# SCH_LM2596_2023-11-16.net
KiCad netlist of a schematic drawn in EasyEDA
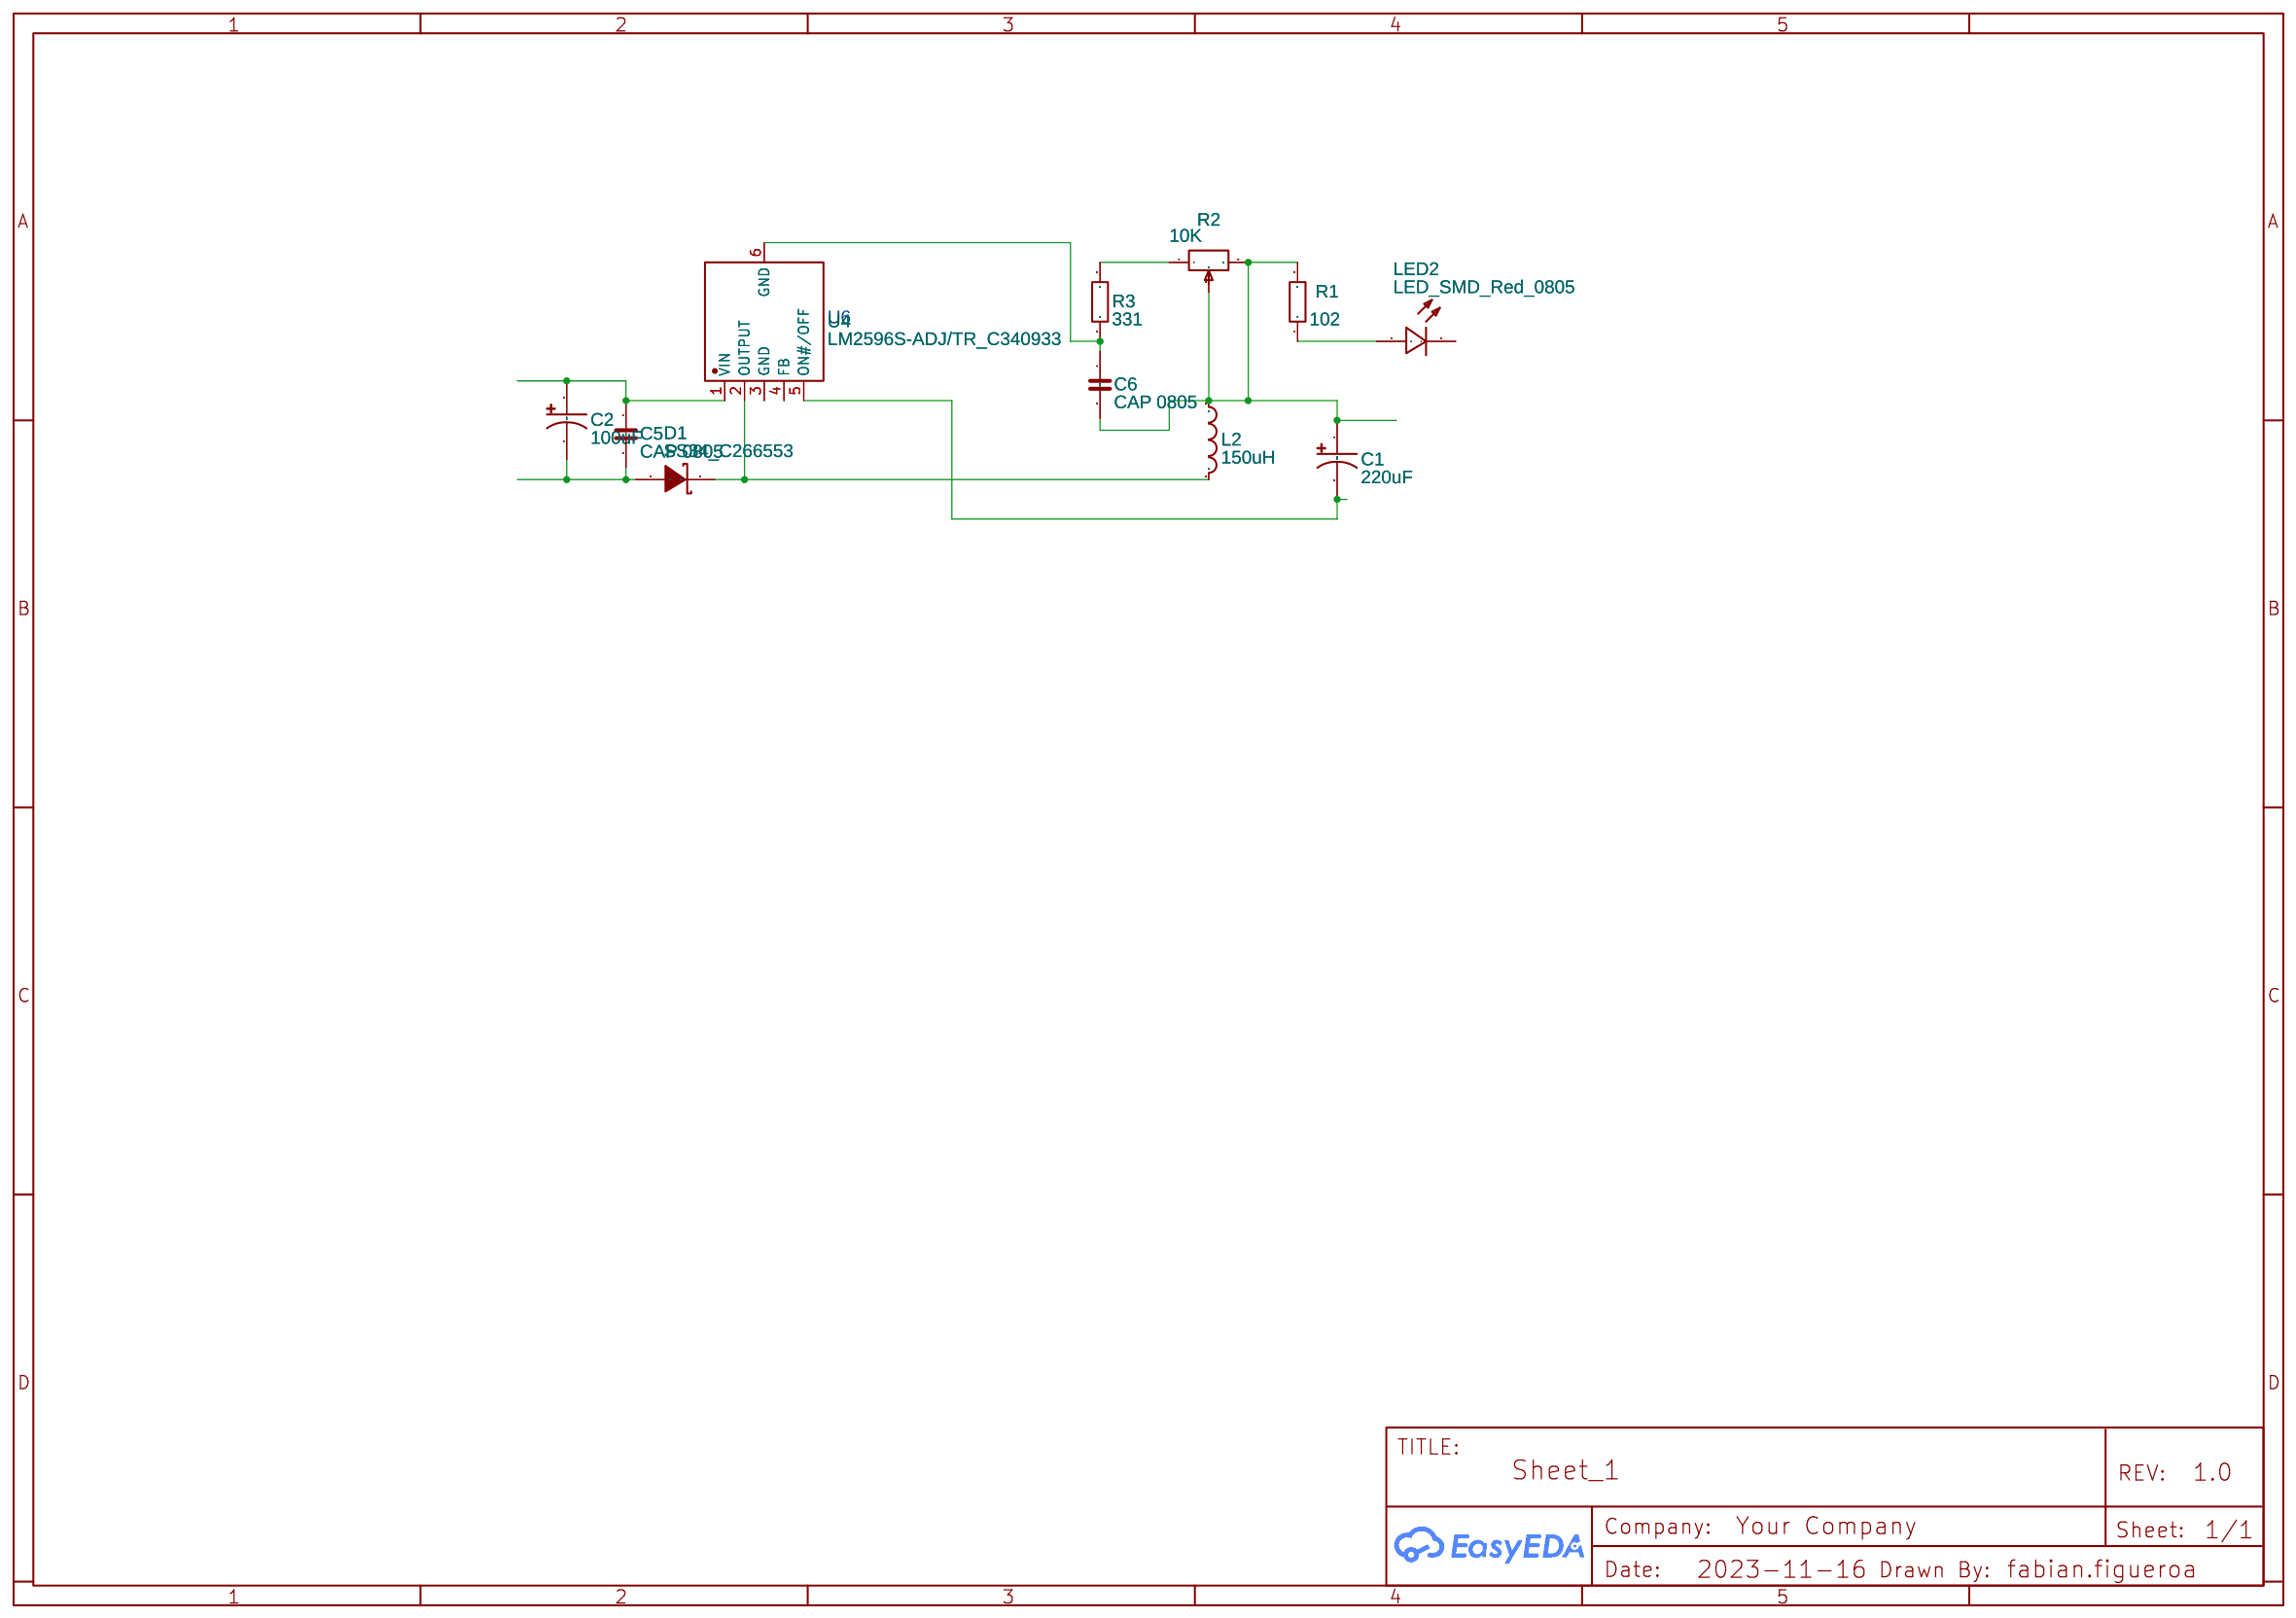
[diagram p0: schematic sheet]

(export (version "E")
  (design (tool "Eeschema 10.0.6"))
  (components
    (comp (ref "C1")
      (value "220uF")
      (fields
        (field (name "Manufacturer Part") "MVK35VC220M8*10_8.0TP")
        (field (name "Manufacturer") "SamYoung Electronics")
      )
      (libsource (lib "") (part "MVK35VC220M8*10_8.0TP"))
    )
    (comp (ref "C2")
      (value "100uF")
      (fields
        (field (name "Manufacturer Part") "BXJ-35V100-8*10")
        (field (name "Manufacturer") "SamYoung Electronics")
      )
      (libsource (lib "") (part "BXJ-35V100-8*10"))
    )
    (comp (ref "C5") (value "CAP 0805") (libsource (lib "") (part "CAP 0805")))
    (comp (ref "C6") (value "CAP 0805") (libsource (lib "") (part "CAP 0805")))
    (comp (ref "D1")
      (value "SS34_C266553")
      (fields
        (field (name "Manufacturer Part") "SS34")
        (field (name "Manufacturer") "Bourne Semicon (Shenzhen)")
      )
      (libsource (lib "") (part "SS34_C266553"))
    )
    (comp (ref "L2")
      (value "150uH")
      (fields (field (name "Manufacturer Part") "CDRH127/LDNP-151MC") (field (name "Manufacturer") "Sumida"))
      (libsource (lib "") (part "CDRH127/LDNP-151MC"))
    )
    (comp (ref "LED2")
      (value "LED_SMD_Red_0805")
      (fields
        (field (name "Manufacturer Part") "17-21SURC/S530-A2/TR8")
        (field (name "Manufacturer") "Everlight Elec")
      )
      (libsource (lib "") (part "LED_SMD_Red_0805"))
    )
    (comp (ref "R1") (value "102") (libsource (lib "") (part "RES 0805")))
    (comp (ref "R2")
      (value "10K")
      (fields (field (name "Manufacturer Part") "3296W-1-103LF") (field (name "Manufacturer") "BOURNS"))
      (libsource (lib "") (part "3296W-1-103LF"))
    )
    (comp (ref "R3") (value "331") (libsource (lib "") (part "RES 0805")))
    (comp (ref "U4")
      (value "LM2596S-ADJ/TR_C340933")
      (fields
        (field (name "Manufacturer Part") "LM2596S-ADJ/TR")
        (field (name "Manufacturer") "Huaguan Semicon")
      )
      (libsource (lib "") (part "LM2596S-ADJ/TR_C340933"))
    )
  )
  (nets
    (net (code "1") (name "Net-(C1-Pad1)") (class "Default")
      (node (ref "C1") (pin "1") (pinfunction "1_1") (pintype "unspecified"))
      (node (ref "C6") (pin "2") (pinfunction "2_2") (pintype "unspecified"))
      (node (ref "L2") (pin "1") (pinfunction "1_1") (pintype "unspecified"))
      (node (ref "R1") (pin "2") (pinfunction "2_2") (pintype "unspecified"))
      (node (ref "R2") (pin "2") (pinfunction "2_2") (pintype "input"))
      (node (ref "R2") (pin "3") (pinfunction "3_3") (pintype "input"))
    )
    (net (code "2") (name "Net-(C6-Pad1)") (class "Default")
      (node (ref "C6") (pin "1") (pinfunction "1_1") (pintype "unspecified"))
      (node (ref "R3") (pin "1") (pinfunction "1_1") (pintype "unspecified"))
      (node (ref "U4") (pin "6") (pinfunction "GND_6") (pintype "unspecified"))
    )
    (net (code "3") (name "Net-(D1-A)") (class "Default")
      (node (ref "C2") (pin "2") (pinfunction "2_2") (pintype "unspecified"))
      (node (ref "C5") (pin "2") (pinfunction "2_2") (pintype "unspecified"))
      (node (ref "D1") (pin "2") (pinfunction "A_2") (pintype "unspecified"))
    )
    (net (code "4") (name "Net-(D1-C)") (class "Default")
      (node (ref "D1") (pin "1") (pinfunction "C_1") (pintype "unspecified"))
      (node (ref "L2") (pin "2") (pinfunction "2_2") (pintype "unspecified"))
      (node (ref "U4") (pin "2") (pinfunction "OUTPUT_2") (pintype "unspecified"))
    )
    (net (code "5") (name "Net-(LED2-+)") (class "Default")
      (node (ref "LED2") (pin "1") (pinfunction "+_1") (pintype "unspecified"))
      (node (ref "R1") (pin "1") (pinfunction "1_1") (pintype "unspecified"))
    )
    (net (code "6") (name "Net-(R2-Pad1)") (class "Default")
      (node (ref "R2") (pin "1") (pinfunction "1_1") (pintype "input"))
      (node (ref "R3") (pin "2") (pinfunction "2_2") (pintype "unspecified"))
    )
    (net (code "7") (name "Net-(U4-ON#{slash}OFF)") (class "Default")
      (node (ref "C1") (pin "2") (pinfunction "2_2") (pintype "unspecified"))
      (node (ref "U4") (pin "5") (pinfunction "ON#/OFF_5") (pintype "unspecified"))
    )
    (net (code "8") (name "Net-(U4-VIN)") (class "Default")
      (node (ref "C2") (pin "1") (pinfunction "1_1") (pintype "unspecified"))
      (node (ref "C5") (pin "1") (pinfunction "1_1") (pintype "unspecified"))
      (node (ref "U4") (pin "1") (pinfunction "VIN_1") (pintype "unspecified"))
    )
    (net (code "9") (name "unconnected-(LED2---Pad2)") (class "Default")
      (node (ref "LED2") (pin "2") (pinfunction "-_2") (pintype "unspecified"))
    )
    (net (code "10") (name "unconnected-(U4-FB-Pad4)") (class "Default")
      (node (ref "U4") (pin "4") (pinfunction "FB_4") (pintype "unspecified"))
    )
    (net (code "11") (name "unconnected-(U4-GND-Pad3)") (class "Default")
      (node (ref "U4") (pin "3") (pinfunction "GND_3") (pintype "unspecified"))
    )
  )
)
